# Charger_PowerPath.net
KiCad netlist of a schematic drawn in Altium Designer
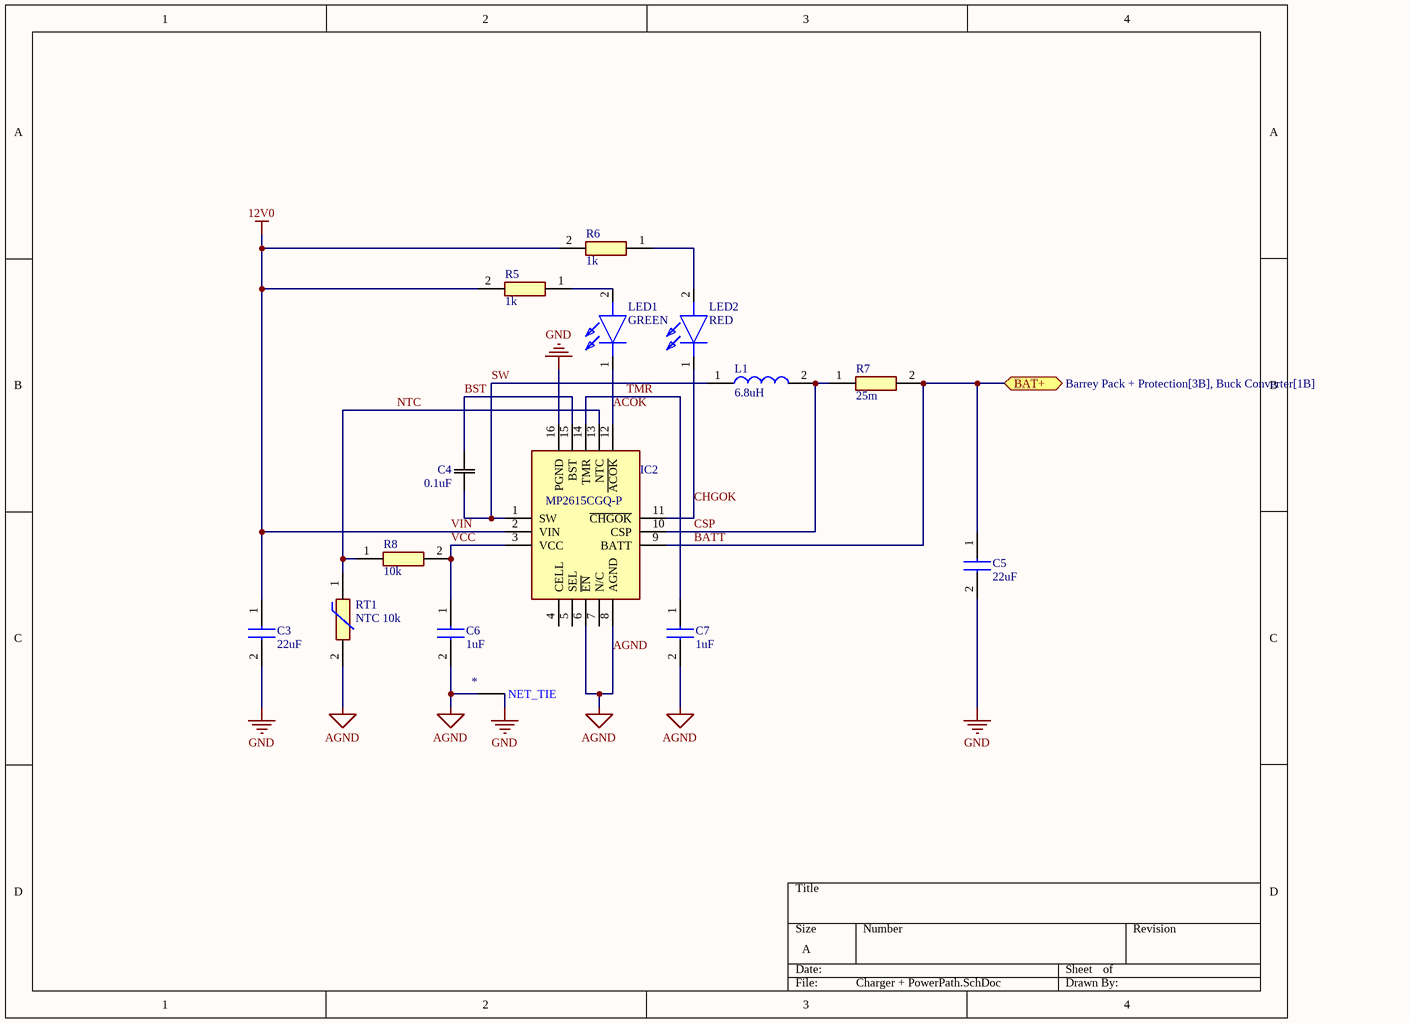
[diagram p0: Charger + PowerPath.SchDoc]

(export (version "E")
  (design (tool "Eeschema 10.0.6"))
  (components
    (comp (ref "*")
      (value "Component_1")
      (footprint "NET_TIE")
      (libsource (lib "Net_Tie") (part "Component_1"))
    )
    (comp (ref "C3")
      (value "22uF")
      (footprint "SamacSys:C2220")
      (description "Capacitor")
      (fields (field (name "MANUFACTURER_PART_NUMBER") "C2220C226J3RACTU"))
      (libsource (lib "*") (part "C2220C226J3RACTU"))
    )
    (comp (ref "C4")
      (value "0.1uF")
      (footprint "CAPC220145_88N_KEM")
      (description "SMD Comm X7R, Ceramic, 0.1 uF, 10%, 50 VDC, X7R, SMD, MLCC, Temperature Stable, Class II, 0805")
      (fields
        (field (name "MANUFACTURER_PART_NUMBER") "C0805C104K5RACTU")
        (field (name "COPYRIGHT") "Copyright (C) 2025 Ultra Librarian. All rights reserved.")
      )
      (libsource (lib "C0805C104K5RACTU") (part "C0805C104K5RACTU"))
    )
    (comp (ref "C5")
      (value "22uF")
      (footprint "SamacSys:C2220")
      (description "Capacitor")
      (fields (field (name "MANUFACTURER_PART_NUMBER") "C2220C226J3RACTU"))
      (libsource (lib "*") (part "C2220C226J3RACTU"))
    )
    (comp (ref "C6")
      (value "1uF")
      (footprint "SamacSys:C0805")
      (description "Capacitor")
      (fields
        (field (name "MANUFACTURER_PART_NUMBER") "C0805C105J4RAC7210")
        (field (name "MOUSER PART NUMBER") "80-C0805C105J4RACLR")
      )
      (libsource (lib "*") (part "C0805C105J4RAC7210"))
    )
    (comp (ref "C7")
      (value "1uF")
      (footprint "SamacSys:C0805")
      (description "Capacitor")
      (fields
        (field (name "MANUFACTURER_PART_NUMBER") "C0805C105J4RAC7210")
        (field (name "MOUSER PART NUMBER") "80-C0805C105J4RACLR")
      )
      (libsource (lib "*") (part "C0805C105J4RAC7210"))
    )
    (comp (ref "IC2")
      (value "MP2615CGQ-P")
      (footprint "SamacSys:MP2615CGQP")
      (description "Integrated Circuit")
      (fields (field (name "MOUSER PART NUMBER") "946-MP2615CGQ-P"))
      (libsource (lib "*") (part "MP2615CGQ-P"))
    )
    (comp (ref "L1")
      (value "6.8uH")
      (footprint "SamacSys:INDPM6965X300N")
      (description "Inductor")
      (fields
        (field (name "MANUFACTURER_PART_NUMBER") "IHLP2525CZER6R8M11")
        (field (name "MOUSER PART NUMBER") "70-IHLP2525CZER6R8M")
      )
      (libsource (lib "*") (part "IHLP2525CZER6R8M11"))
    )
    (comp (ref "LED1")
      (value "GREEN")
      (footprint "SamacSys:LEDC2012X110N")
      (description "LED")
      (fields
        (field (name "MANUFACTURER_PART_NUMBER") "LTST-C170KGKT")
        (field (name "MOUSER PART NUMBER") "859-LTST-C170KGKT")
      )
      (libsource (lib "*") (part "LTST-C170KGKT"))
    )
    (comp (ref "LED2")
      (value "RED")
      (footprint "SamacSys:LEDC2012X120N")
      (description "LED")
      (fields
        (field (name "MANUFACTURER_PART_NUMBER") "LTST-C170KRKT")
        (field (name "MOUSER PART NUMBER") "859-LTST-C170KRKT")
      )
      (libsource (lib "*") (part "LTST-C170KRKT"))
    )
    (comp (ref "R5")
      (value "1k")
      (footprint "SamacSys:RESC2012X60N")
      (description "Resistor")
      (fields
        (field (name "MANUFACTURER_PART_NUMBER") "RT0805FRE071KL")
        (field (name "MOUSER PART NUMBER") "603-RT0805FRE071KL")
      )
      (libsource (lib "*") (part "RT0805FRE071KL"))
    )
    (comp (ref "R6")
      (value "1k")
      (footprint "SamacSys:RESC2012X60N")
      (description "Resistor")
      (fields
        (field (name "MANUFACTURER_PART_NUMBER") "RT0805FRE071KL")
        (field (name "MOUSER PART NUMBER") "603-RT0805FRE071KL")
      )
      (libsource (lib "*") (part "RT0805FRE071KL"))
    )
    (comp (ref "R7")
      (value "25m")
      (footprint "SamacSys:RESC6332X71N")
      (description "Resistor")
      (fields
        (field (name "MANUFACTURER_PART_NUMBER") "WSL2512R0250FEA")
        (field (name "MOUSER PART NUMBER") "71-WSL2512R0250FEA")
      )
      (libsource (lib "*") (part "WSL2512R0250FEA"))
    )
    (comp (ref "R8")
      (value "10k")
      (footprint "SamacSys:RESC2012X60N")
      (description "Resistor")
      (fields
        (field (name "MANUFACTURER_PART_NUMBER") "RT0805FRE0710KL")
        (field (name "MOUSER PART NUMBER") "603-RT0805FRE0710KL")
      )
      (libsource (lib "*") (part "RT0805FRE0710KL"))
    )
    (comp (ref "RT1")
      (value "NTC 10k")
      (footprint "SamacSys:THRMC2012X130N")
      (description "Thermistor")
      (fields
        (field (name "MANUFACTURER_PART_NUMBER") "B57442V5103H062")
        (field (name "MOUSER PART NUMBER") "871-B57442V5103H62")
      )
      (libsource (lib "*") (part "B57442V5103H062"))
    )
  )
  (nets
    (net (code "1") (name "/ACOK") (class "Default")
      (node (ref "IC2") (pin "12") (pinfunction "~{ACOK}_12") (pintype "passive"))
      (node (ref "LED1") (pin "1") (pinfunction "K_1") (pintype "passive"))
    )
    (net (code "2") (name "/BATT") (class "Default")
      (node (ref "C5") (pin "1") (pinfunction "1_1") (pintype "passive"))
      (node (ref "IC2") (pin "9") (pinfunction "BATT_9") (pintype "passive"))
      (node (ref "R7") (pin "2") (pinfunction "2_2") (pintype "passive"))
    )
    (net (code "3") (name "/BST") (class "Default")
      (node (ref "C4") (pin "2") (pinfunction "2_2") (pintype "passive"))
      (node (ref "IC2") (pin "15") (pinfunction "BST_15") (pintype "passive"))
    )
    (net (code "4") (name "/CHGOK") (class "Default")
      (node (ref "IC2") (pin "11") (pinfunction "~{CHGOK}_11") (pintype "passive"))
      (node (ref "LED2") (pin "1") (pinfunction "K_1") (pintype "passive"))
    )
    (net (code "5") (name "/CSP") (class "Default")
      (node (ref "IC2") (pin "10") (pinfunction "CSP_10") (pintype "passive"))
      (node (ref "L1") (pin "2") (pinfunction "2_2") (pintype "passive"))
      (node (ref "R7") (pin "1") (pinfunction "1_1") (pintype "passive"))
    )
    (net (code "6") (name "/NTC") (class "Default")
      (node (ref "IC2") (pin "13") (pinfunction "NTC_13") (pintype "passive"))
      (node (ref "R8") (pin "1") (pinfunction "1_1") (pintype "passive"))
      (node (ref "RT1") (pin "1") (pinfunction "1_1") (pintype "passive"))
    )
    (net (code "7") (name "/SW") (class "Default")
      (node (ref "C4") (pin "1") (pinfunction "1_1") (pintype "passive"))
      (node (ref "IC2") (pin "1") (pinfunction "SW_1") (pintype "passive"))
      (node (ref "L1") (pin "1") (pinfunction "1_1") (pintype "passive"))
    )
    (net (code "8") (name "/TMR") (class "Default")
      (node (ref "C7") (pin "1") (pinfunction "1_1") (pintype "passive"))
      (node (ref "IC2") (pin "14") (pinfunction "TMR_14") (pintype "passive"))
    )
    (net (code "9") (name "/VCC") (class "Default")
      (node (ref "C6") (pin "1") (pinfunction "1_1") (pintype "passive"))
      (node (ref "IC2") (pin "3") (pinfunction "VCC_3") (pintype "passive"))
      (node (ref "R8") (pin "2") (pinfunction "2_2") (pintype "passive"))
    )
    (net (code "10") (name "12V0") (class "Default")
      (node (ref "C3") (pin "1") (pinfunction "1_1") (pintype "passive"))
      (node (ref "IC2") (pin "2") (pinfunction "VIN_2") (pintype "passive"))
      (node (ref "R5") (pin "2") (pinfunction "2_2") (pintype "passive"))
      (node (ref "R6") (pin "2") (pinfunction "2_2") (pintype "passive"))
    )
    (net (code "11") (name "AGND") (class "Default")
      (node (ref "*") (pin "N1") (pinfunction "NET_TIE_N1") (pintype "passive"))
      (node (ref "C6") (pin "2") (pinfunction "2_2") (pintype "passive"))
      (node (ref "C7") (pin "2") (pinfunction "2_2") (pintype "passive"))
      (node (ref "IC2") (pin "6") (pinfunction "~{EN}_6") (pintype "passive"))
      (node (ref "IC2") (pin "8") (pinfunction "AGND_8") (pintype "passive"))
      (node (ref "RT1") (pin "2") (pinfunction "2_2") (pintype "passive"))
    )
    (net (code "12") (name "GND") (class "Default")
      (node (ref "*") (pin "N2") (pinfunction "NET_TIE_N2") (pintype "passive"))
      (node (ref "C3") (pin "2") (pinfunction "2_2") (pintype "passive"))
      (node (ref "C5") (pin "2") (pinfunction "2_2") (pintype "passive"))
      (node (ref "IC2") (pin "16") (pinfunction "PGND_16") (pintype "passive"))
    )
    (net (code "13") (name "Net-(LED1-A)") (class "Default")
      (node (ref "LED1") (pin "2") (pinfunction "A_2") (pintype "passive"))
      (node (ref "R5") (pin "1") (pinfunction "1_1") (pintype "passive"))
    )
    (net (code "14") (name "Net-(LED2-A)") (class "Default")
      (node (ref "LED2") (pin "2") (pinfunction "A_2") (pintype "passive"))
      (node (ref "R6") (pin "1") (pinfunction "1_1") (pintype "passive"))
    )
    (net (code "15") (name "unconnected-(IC2-CELL-Pad4)") (class "Default")
      (node (ref "IC2") (pin "4") (pinfunction "CELL_4") (pintype "passive"))
    )
    (net (code "16") (name "unconnected-(IC2-N{slash}C-Pad7)") (class "Default")
      (node (ref "IC2") (pin "7") (pinfunction "N/C_7") (pintype "passive"))
    )
    (net (code "17") (name "unconnected-(IC2-SEL-Pad5)") (class "Default")
      (node (ref "IC2") (pin "5") (pinfunction "SEL_5") (pintype "passive"))
    )
  )
)
